# controller_board.net
KiCad netlist of a schematic drawn in EAGLE
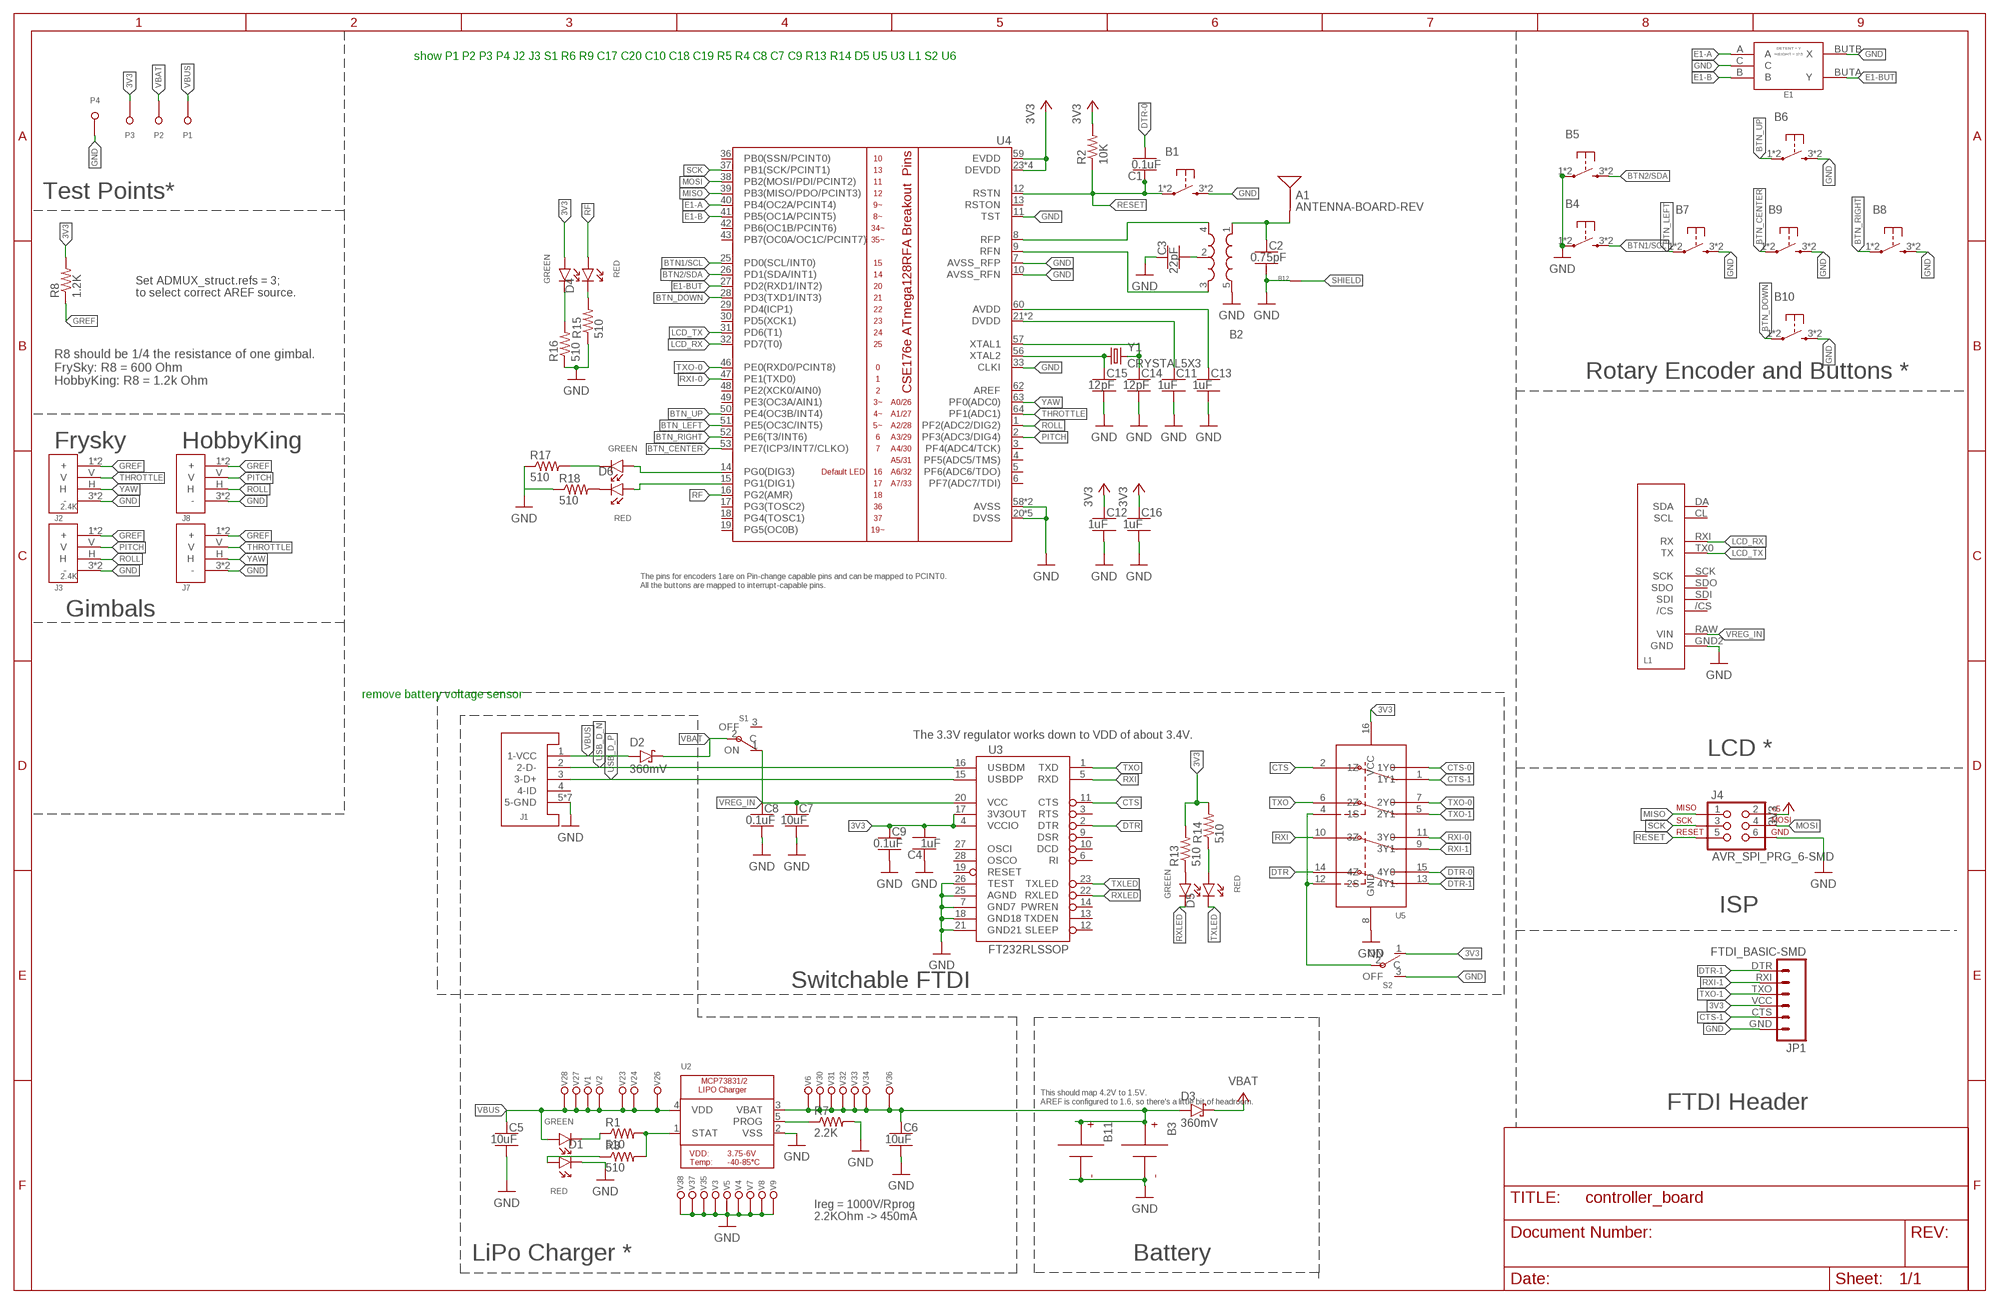
[diagram p0: schematic, sheet 1]

(export (version "E")
  (design (tool "Eeschema 10.0.6"))
  (components
    (comp (ref "A1")
      (value "ANTENNA-BOARD-REV")
      (footprint "eagle-import:ANT_PCB_2.4GHZ_NRF8001_1.6MM_1OZ_REV")
      (fields (field (name "CREATOR") "Swanson"))
      (libsource (lib "eagle-import") (part "ANTENNA-BOARD-REV"))
    )
    (comp (ref "B1")
      (value "PUSHBUTTON_-4.5X4.5")
      (footprint "eagle-import:4.5MM_TACTILE_SWITCH_TL3305AF160QG")
      (fields (field (name "CREATOR") "Swanson"))
      (libsource (lib "eagle-import") (part "PUSHBUTTON_-4.5X4.5"))
    )
    (comp (ref "B2")
      (value "BALUN0805")
      (footprint "eagle-import:BALUN")
      (fields
        (field (name "MFR") "Wurth Electronics Inc")
        (field (name "MPN") "748421245")
        (field (name "CREATOR") "Swanson")
        (field (name "REVIEWER") "Swanson")
      )
      (libsource (lib "eagle-import") (part "BALUN0805"))
    )
    (comp (ref "B3")
      (value "BATTERY-SPRING-SMD")
      (footprint "eagle-import:WIRE-TERMINAL-1X2-2.5MM-SMD-AVX-009276002021106")
      (libsource (lib "eagle-import") (part "BATTERY-SPRING-SMD"))
    )
    (comp (ref "B4")
      (value "PUSHBUTTON_-4.5X4.5")
      (footprint "eagle-import:4.5MM_TACTILE_SWITCH_TL3305AF160QG")
      (fields (field (name "CREATOR") "Swanson"))
      (libsource (lib "eagle-import") (part "PUSHBUTTON_-4.5X4.5"))
    )
    (comp (ref "B5")
      (value "PUSHBUTTON_-4.5X4.5")
      (footprint "eagle-import:4.5MM_TACTILE_SWITCH_TL3305AF160QG")
      (fields (field (name "CREATOR") "Swanson"))
      (libsource (lib "eagle-import") (part "PUSHBUTTON_-4.5X4.5"))
    )
    (comp (ref "B6")
      (value "PUSHBUTTON_-4.5X4.5")
      (footprint "eagle-import:4.5MM_TACTILE_SWITCH_TL3305AF160QG")
      (fields (field (name "CREATOR") "Swanson"))
      (libsource (lib "eagle-import") (part "PUSHBUTTON_-4.5X4.5"))
    )
    (comp (ref "B7")
      (value "PUSHBUTTON_-4.5X4.5")
      (footprint "eagle-import:4.5MM_TACTILE_SWITCH_TL3305AF160QG")
      (fields (field (name "CREATOR") "Swanson"))
      (libsource (lib "eagle-import") (part "PUSHBUTTON_-4.5X4.5"))
    )
    (comp (ref "B8")
      (value "PUSHBUTTON_-4.5X4.5")
      (footprint "eagle-import:4.5MM_TACTILE_SWITCH_TL3305AF160QG")
      (fields (field (name "CREATOR") "Swanson"))
      (libsource (lib "eagle-import") (part "PUSHBUTTON_-4.5X4.5"))
    )
    (comp (ref "B9")
      (value "PUSHBUTTON_-4.5X4.5")
      (footprint "eagle-import:4.5MM_TACTILE_SWITCH_TL3305AF160QG")
      (fields (field (name "CREATOR") "Swanson"))
      (libsource (lib "eagle-import") (part "PUSHBUTTON_-4.5X4.5"))
    )
    (comp (ref "B10")
      (value "PUSHBUTTON_-4.5X4.5")
      (footprint "eagle-import:4.5MM_TACTILE_SWITCH_TL3305AF160QG")
      (fields (field (name "CREATOR") "Swanson"))
      (libsource (lib "eagle-import") (part "PUSHBUTTON_-4.5X4.5"))
    )
    (comp (ref "B11")
      (value "BATTERY-SCREW-TERMINAL")
      (footprint "eagle-import:SCREW-TERMINAL-1X2-2.54MM")
      (fields (field (name "CREATOR") "Swanson"))
      (libsource (lib "eagle-import") (part "BATTERY-SCREW-TERMINAL"))
    )
    (comp (ref "B12")
      (value "NET_BRIDGE")
      (footprint "eagle-import:NET_BRIDGE")
      (fields (field (name "CREATOR") "Michael Gonzalez"))
      (libsource (lib "eagle-import") (part "NET_BRIDGE"))
    )
    (comp (ref "C1")
      (value "0.1uF")
      (footprint "eagle-import:CAPC2012X140_HS")
      (fields
        (field (name "MFR") "TDK")
        (field (name "MPN") "C2012X7R2A104K125AA")
        (field (name "CREATOR") "Swanson")
        (field (name "REVIEWER") "Swanson")
      )
      (libsource (lib "eagle-import") (part "CAPACITOR-NP_SMD-2012-0805_CERAMIC-0.1UF"))
    )
    (comp (ref "C2")
      (value "0.75pF")
      (footprint "eagle-import:CAPC2012X140_HS")
      (fields
        (field (name "MFR") "Murata Electronics North America")
        (field (name "MPN") "GQM2195C2AR75CB01D")
        (field (name "CREATOR") "Swanson")
        (field (name "REVIEWER") "Swanson")
      )
      (libsource (lib "eagle-import") (part "CAPACITOR-NP_SMD-2012-0805_CERAMIC-0.75PF"))
    )
    (comp (ref "C3")
      (value "22pF")
      (footprint "eagle-import:CAPC2012X140_HS")
      (fields
        (field (name "MFR") "Murata Electronics North America")
        (field (name "MPN") "GRM21A5C2E220JW01D")
        (field (name "CREATOR") "Swanson")
        (field (name "REVIEWER") "Swanson")
      )
      (libsource (lib "eagle-import") (part "CAPACITOR-NP_SMD-2012-0805_CERAMIC-22PF"))
    )
    (comp (ref "C4")
      (value "1uF")
      (footprint "eagle-import:CAPC2012X140_HS")
      (fields
        (field (name "MFR") "Taiyo Yuden")
        (field (name "MPN") "TMK212B7105KG-T")
        (field (name "CREATOR") "Swanson")
        (field (name "REVIEWER") "Swanson")
      )
      (libsource (lib "eagle-import") (part "CAPACITOR-NP_SMD-2012-0805_CERAMIC-1UF"))
    )
    (comp (ref "C5")
      (value "10uF")
      (footprint "eagle-import:CAPC2012X140_HS")
      (fields (field (name "CREATOR") "Swanson") (field (name "REVIEWER") "Swanson"))
      (libsource (lib "eagle-import") (part "CAPACITOR-NP_SMD-2012-0805_CERAMIC-10UF"))
    )
    (comp (ref "C6")
      (value "10uF")
      (footprint "eagle-import:CAPC2012X140_HS")
      (fields (field (name "CREATOR") "Swanson") (field (name "REVIEWER") "Swanson"))
      (libsource (lib "eagle-import") (part "CAPACITOR-NP_SMD-2012-0805_CERAMIC-10UF"))
    )
    (comp (ref "C7")
      (value "10uF")
      (footprint "eagle-import:CAPC2012X140_HS")
      (fields (field (name "CREATOR") "Swanson") (field (name "REVIEWER") "Swanson"))
      (libsource (lib "eagle-import") (part "CAPACITOR-NP_SMD-2012-0805_CERAMIC-10UF"))
    )
    (comp (ref "C8")
      (value "0.1uF")
      (footprint "eagle-import:CAPC2012X140_HS")
      (fields
        (field (name "MFR") "TDK")
        (field (name "MPN") "C2012X7R2A104K125AA")
        (field (name "CREATOR") "Swanson")
        (field (name "REVIEWER") "Swanson")
      )
      (libsource (lib "eagle-import") (part "CAPACITOR-NP_SMD-2012-0805_CERAMIC-0.1UF"))
    )
    (comp (ref "C9")
      (value "0.1uF")
      (footprint "eagle-import:CAPC2012X140_HS")
      (fields
        (field (name "MFR") "TDK")
        (field (name "MPN") "C2012X7R2A104K125AA")
        (field (name "CREATOR") "Swanson")
        (field (name "REVIEWER") "Swanson")
      )
      (libsource (lib "eagle-import") (part "CAPACITOR-NP_SMD-2012-0805_CERAMIC-0.1UF"))
    )
    (comp (ref "C11")
      (value "1uF")
      (footprint "eagle-import:CAPC2012X140_HS")
      (fields
        (field (name "MFR") "Taiyo Yuden")
        (field (name "MPN") "TMK212B7105KG-T")
        (field (name "CREATOR") "Swanson")
        (field (name "REVIEWER") "Swanson")
      )
      (libsource (lib "eagle-import") (part "CAPACITOR-NP_SMD-2012-0805_CERAMIC-1UF"))
    )
    (comp (ref "C12")
      (value "1uF")
      (footprint "eagle-import:CAPC2012X140_HS")
      (fields
        (field (name "MFR") "Taiyo Yuden")
        (field (name "MPN") "TMK212B7105KG-T")
        (field (name "CREATOR") "Swanson")
        (field (name "REVIEWER") "Swanson")
      )
      (libsource (lib "eagle-import") (part "CAPACITOR-NP_SMD-2012-0805_CERAMIC-1UF"))
    )
    (comp (ref "C13")
      (value "1uF")
      (footprint "eagle-import:CAPC2012X140_HS")
      (fields
        (field (name "MFR") "Taiyo Yuden")
        (field (name "MPN") "TMK212B7105KG-T")
        (field (name "CREATOR") "Swanson")
        (field (name "REVIEWER") "Swanson")
      )
      (libsource (lib "eagle-import") (part "CAPACITOR-NP_SMD-2012-0805_CERAMIC-1UF"))
    )
    (comp (ref "C14")
      (value "12pF")
      (footprint "eagle-import:CAPC2012X140_HS")
      (fields
        (field (name "MFR") "Murata Electronics North America")
        (field (name "MPN") "GRM21A5C2E120JW01D")
        (field (name "CREATOR") "Swanson")
        (field (name "REVIEWER") "Swanson")
      )
      (libsource (lib "eagle-import") (part "CAPACITOR-NP_SMD-2012-0805_CERAMIC-12PF"))
    )
    (comp (ref "C15")
      (value "12pF")
      (footprint "eagle-import:CAPC2012X140_HS")
      (fields
        (field (name "MFR") "Murata Electronics North America")
        (field (name "MPN") "GRM21A5C2E120JW01D")
        (field (name "CREATOR") "Swanson")
        (field (name "REVIEWER") "Swanson")
      )
      (libsource (lib "eagle-import") (part "CAPACITOR-NP_SMD-2012-0805_CERAMIC-12PF"))
    )
    (comp (ref "C16")
      (value "1uF")
      (footprint "eagle-import:CAPC2012X140_HS")
      (fields
        (field (name "MFR") "Taiyo Yuden")
        (field (name "MPN") "TMK212B7105KG-T")
        (field (name "CREATOR") "Swanson")
        (field (name "REVIEWER") "Swanson")
      )
      (libsource (lib "eagle-import") (part "CAPACITOR-NP_SMD-2012-0805_CERAMIC-1UF"))
    )
    (comp (ref "D1")
      (value "LED-2X-GREEN/RED")
      (footprint "eagle-import:LED-2X-LTST-C155")
      (fields
        (field (name "COLOR2") "RED")
        (field (name "COLOR1") "GREEN")
        (field (name "CREATOR") "Swanson")
      )
      (libsource (lib "eagle-import") (part "LED-2X-GREEN/RED"))
    )
    (comp (ref "D2")
      (value "360mV")
      (footprint "eagle-import:SOD3716X135_HS")
      (fields
        (field (name "MFR") "Toshiba Semiconductor and Storage")
        (field (name "MPN") "CRS08(TE85L,Q,M)")
        (field (name "CREATOR") "Swanson")
        (field (name "REVIEWER") "Swanson")
      )
      (libsource (lib "eagle-import") (part "DIODE-SCHOTTKY_SMD-SOD123-360MV"))
    )
    (comp (ref "D3")
      (value "360mV")
      (footprint "eagle-import:SOD3716X135_HS")
      (fields
        (field (name "MFR") "Toshiba Semiconductor and Storage")
        (field (name "MPN") "CRS08(TE85L,Q,M)")
        (field (name "CREATOR") "Swanson")
        (field (name "REVIEWER") "Swanson")
      )
      (libsource (lib "eagle-import") (part "DIODE-SCHOTTKY_SMD-SOD123-360MV"))
    )
    (comp (ref "D4")
      (value "LED-2X-GREEN/RED")
      (footprint "eagle-import:LED-2X-LTST-C155")
      (fields
        (field (name "COLOR2") "RED")
        (field (name "COLOR1") "GREEN")
        (field (name "CREATOR") "Swanson")
      )
      (libsource (lib "eagle-import") (part "LED-2X-GREEN/RED"))
    )
    (comp (ref "D5")
      (value "LED-2X-GREEN/RED")
      (footprint "eagle-import:LED-2X-LTST-C155")
      (fields
        (field (name "COLOR2") "RED")
        (field (name "COLOR1") "GREEN")
        (field (name "CREATOR") "Swanson")
      )
      (libsource (lib "eagle-import") (part "LED-2X-GREEN/RED"))
    )
    (comp (ref "D6")
      (value "LED-2X-GREEN/RED")
      (footprint "eagle-import:LED-2X-LTST-C155")
      (fields
        (field (name "COLOR2") "RED")
        (field (name "COLOR1") "GREEN")
        (field (name "CREATOR") "Swanson")
      )
      (libsource (lib "eagle-import") (part "LED-2X-GREEN/RED"))
    )
    (comp (ref "E1")
      (value "ROTARY-ENCODER-W/BUTTON-BOURNS-PEC12R-4217F")
      (footprint "eagle-import:BOURNS-PEC12R")
      (fields (field (name "DETENT") "Y") (field (name "HEIGHT") "17.5") (field (name "CREATOR") "Swanson"))
      (libsource (lib "eagle-import") (part "ROTARY-ENCODER-W/BUTTON-BOURNS-PEC12R-4217F"))
    )
    (comp (ref "J1")
      (value "USB-MICROA-AMPHENOL-10118192-0001LF")
      (footprint "eagle-import:USB-MICROA-10118192-0001LF")
      (fields (field (name "CREATOR") "Swanson"))
      (libsource (lib "eagle-import") (part "USB-MICROA-AMPHENOL-10118192-0001LF"))
    )
    (comp (ref "J2")
      (value "2.4K")
      (footprint "eagle-import:JST-13-PTH")
      (fields (field (name "CREATOR") "Swanson"))
      (libsource (lib "eagle-import") (part "FRSKY-GIMBAL-FRYSKY"))
    )
    (comp (ref "J3")
      (value "2.4K")
      (footprint "eagle-import:JST-13-PTH")
      (fields (field (name "SPICEPREFIX") "E") (field (name "CREATOR") "Swanson"))
      (libsource (lib "eagle-import") (part "FRSKY-GIMBAL-FRYSKY"))
    )
    (comp (ref "J4")
      (value "AVR_SPI_PRG_6-SMD")
      (footprint "eagle-import:2X3-SMD")
      (fields (field (name "CREATOR") "Swanson"))
      (libsource (lib "eagle-import") (part "AVR_SPI_PRG_6-SMD"))
    )
    (comp (ref "J7")
      (value "FRSKY-GIMBAL-2X-SERVO-SMD")
      (footprint "eagle-import:2X-SERVO-SMD")
      (libsource (lib "eagle-import") (part "FRSKY-GIMBAL-2X-SERVO-SMD"))
    )
    (comp (ref "J8")
      (value "FRSKY-GIMBAL-2X-SERVO-SMD")
      (footprint "eagle-import:2X-SERVO-SMD")
      (libsource (lib "eagle-import") (part "FRSKY-GIMBAL-2X-SERVO-SMD"))
    )
    (comp (ref "JP1")
      (value "FTDI_BASIC-SMD")
      (footprint "eagle-import:FTDI-BASIC-SMD")
      (libsource (lib "eagle-import") (part "FTDI_BASIC-SMD"))
    )
    (comp (ref "L1")
      (value "SPARKFUN_SERLCD_SERIAL_REDUCED-SMD")
      (footprint "eagle-import:SPARKFUN_SERLCD_16X2_REDUCED_SMD")
      (fields (field (name "CREATOR") "Swanson"))
      (libsource (lib "eagle-import") (part "SPARKFUN_SERLCD_SERIAL_REDUCED-SMD"))
    )
    (comp (ref "P1")
      (value "TEST-POINT")
      (footprint "eagle-import:TEST-POINT-KEYSTONE-5000")
      (fields (field (name "CREATOR") "Swanson"))
      (libsource (lib "eagle-import") (part "TEST-POINT"))
    )
    (comp (ref "P2")
      (value "TEST-POINT")
      (footprint "eagle-import:TEST-POINT-KEYSTONE-5000")
      (fields (field (name "CREATOR") "Swanson"))
      (libsource (lib "eagle-import") (part "TEST-POINT"))
    )
    (comp (ref "P3")
      (value "TEST-POINT")
      (footprint "eagle-import:TEST-POINT-KEYSTONE-5000")
      (fields (field (name "CREATOR") "Swanson"))
      (libsource (lib "eagle-import") (part "TEST-POINT"))
    )
    (comp (ref "P4")
      (value "TEST-POINT")
      (footprint "eagle-import:TEST-POINT-KEYSTONE-5000")
      (fields (field (name "CREATOR") "Swanson"))
      (libsource (lib "eagle-import") (part "TEST-POINT"))
    )
    (comp (ref "R1")
      (value "510")
      (footprint "eagle-import:RESC2012X60_HS")
      (fields (field (name "CREATOR") "SWANSON"))
      (libsource (lib "eagle-import") (part "RESISTOR_SMD-2012-0805-510"))
    )
    (comp (ref "R2")
      (value "10K")
      (footprint "eagle-import:RESC2012X60_HS")
      (fields
        (field (name "MFR") "Yageo")
        (field (name "MPN") "RC0805JR-0710KL")
        (field (name "CREATOR") "Swanson")
        (field (name "REVIEWER") "Swanson")
      )
      (libsource (lib "eagle-import") (part "RESISTOR_SMD-2012-0805-10K"))
    )
    (comp (ref "R3")
      (value "510")
      (footprint "eagle-import:RESC2012X60_HS")
      (fields (field (name "CREATOR") "SWANSON"))
      (libsource (lib "eagle-import") (part "RESISTOR_SMD-2012-0805-510"))
    )
    (comp (ref "R7")
      (value "2.2K")
      (footprint "eagle-import:RESC2012X60_HS")
      (fields (field (name "CREATOR") "SWANSON"))
      (libsource (lib "eagle-import") (part "RESISTOR_SMD-2012-0805-2.2K"))
    )
    (comp (ref "R8")
      (value "1.2K")
      (footprint "eagle-import:RESC2012X60_HS")
      (fields (field (name "CREATOR") "Swanson"))
      (libsource (lib "eagle-import") (part "RESISTOR_SMD-2012-0805-1.2K"))
    )
    (comp (ref "R13")
      (value "510")
      (footprint "eagle-import:RESC2012X60_HS")
      (fields (field (name "CREATOR") "SWANSON"))
      (libsource (lib "eagle-import") (part "RESISTOR_SMD-2012-0805-510"))
    )
    (comp (ref "R14")
      (value "510")
      (footprint "eagle-import:RESC2012X60_HS")
      (fields (field (name "CREATOR") "SWANSON"))
      (libsource (lib "eagle-import") (part "RESISTOR_SMD-2012-0805-510"))
    )
    (comp (ref "R15")
      (value "510")
      (footprint "eagle-import:RESC2012X60_HS")
      (fields (field (name "CREATOR") "SWANSON"))
      (libsource (lib "eagle-import") (part "RESISTOR_SMD-2012-0805-510"))
    )
    (comp (ref "R16")
      (value "510")
      (footprint "eagle-import:RESC2012X60_HS")
      (fields (field (name "CREATOR") "SWANSON"))
      (libsource (lib "eagle-import") (part "RESISTOR_SMD-2012-0805-510"))
    )
    (comp (ref "R17")
      (value "510")
      (footprint "eagle-import:RESC2012X60_HS")
      (fields (field (name "CREATOR") "SWANSON"))
      (libsource (lib "eagle-import") (part "RESISTOR_SMD-2012-0805-510"))
    )
    (comp (ref "R18")
      (value "510")
      (footprint "eagle-import:RESC2012X60_HS")
      (fields (field (name "CREATOR") "SWANSON"))
      (libsource (lib "eagle-import") (part "RESISTOR_SMD-2012-0805-510"))
    )
    (comp (ref "S1")
      (value "POWER-SWITCH-MFS201N-9-Z-SMD-VERTICAL")
      (footprint "eagle-import:JS102011JCQN")
      (fields (field (name "CREATOR") "Swanson"))
      (libsource (lib "eagle-import") (part "POWER-SWITCH-MFS201N-9-Z-SMD-VERTICAL"))
    )
    (comp (ref "S2")
      (value "POWER-SWITCH-MFS201N-9-Z-SMD-VERTICAL")
      (footprint "eagle-import:JS102011JCQN")
      (fields (field (name "CREATOR") "Swanson"))
      (libsource (lib "eagle-import") (part "POWER-SWITCH-MFS201N-9-Z-SMD-VERTICAL"))
    )
    (comp (ref "U2")
      (value "MCP73831T-2ACI/OT")
      (footprint "eagle-import:SOT23-5")
      (fields (field (name "CREATOR") "Adafruit"))
      (libsource (lib "eagle-import") (part "MCP73831/2"))
    )
    (comp (ref "U3")
      (value "FT232RLSSOP")
      (footprint "eagle-import:SSOP28DB")
      (fields (field (name "CREATOR") "Swanson"))
      (libsource (lib "eagle-import") (part "FT232RLSSOP"))
    )
    (comp (ref "U4")
      (value "ATMEGA128RFA1")
      (footprint "eagle-import:QFN-64")
      (fields
        (field (name "MFR") "Atmel")
        (field (name "MPN") "ATMEGA128RFA1-ZUR00")
        (field (name "CREATOR") "Swanson")
        (field (name "REVIEWER") "Swanson")
      )
      (libsource (lib "eagle-import") (part "ATMEGA128RFA1"))
    )
    (comp (ref "U5")
      (value "DPDT-X2")
      (footprint "eagle-import:SOP65P640X110-16")
      (fields (field (name "CREATOR") "Swanson"))
      (libsource (lib "eagle-import") (part "DPDT-X2"))
    )
    (comp (ref "V1")
      (value "LOCKED-VIA-0.2")
      (footprint "eagle-import:VIA-0.2MM")
      (fields (field (name "CREATOR") "Swanson"))
      (libsource (lib "eagle-import") (part "LOCKED-VIA-0.2"))
    )
    (comp (ref "V2")
      (value "LOCKED-VIA-0.2")
      (footprint "eagle-import:VIA-0.2MM")
      (fields (field (name "CREATOR") "Swanson"))
      (libsource (lib "eagle-import") (part "LOCKED-VIA-0.2"))
    )
    (comp (ref "V3")
      (value "LOCKED-VIA-0.2")
      (footprint "eagle-import:VIA-0.2MM")
      (fields (field (name "CREATOR") "Swanson"))
      (libsource (lib "eagle-import") (part "LOCKED-VIA-0.2"))
    )
    (comp (ref "V4")
      (value "LOCKED-VIA-0.2")
      (footprint "eagle-import:VIA-0.2MM")
      (fields (field (name "CREATOR") "Swanson"))
      (libsource (lib "eagle-import") (part "LOCKED-VIA-0.2"))
    )
    (comp (ref "V5")
      (value "LOCKED-VIA-0.2")
      (footprint "eagle-import:VIA-0.2MM")
      (fields (field (name "CREATOR") "Swanson"))
      (libsource (lib "eagle-import") (part "LOCKED-VIA-0.2"))
    )
    (comp (ref "V6")
      (value "LOCKED-VIA-0.2")
      (footprint "eagle-import:VIA-0.2MM")
      (fields (field (name "CREATOR") "Swanson"))
      (libsource (lib "eagle-import") (part "LOCKED-VIA-0.2"))
    )
    (comp (ref "V7")
      (value "LOCKED-VIA-0.2")
      (footprint "eagle-import:VIA-0.2MM")
      (fields (field (name "CREATOR") "Swanson"))
      (libsource (lib "eagle-import") (part "LOCKED-VIA-0.2"))
    )
    (comp (ref "V8")
      (value "LOCKED-VIA-0.2")
      (footprint "eagle-import:VIA-0.2MM")
      (fields (field (name "CREATOR") "Swanson"))
      (libsource (lib "eagle-import") (part "LOCKED-VIA-0.2"))
    )
    (comp (ref "V9")
      (value "LOCKED-VIA-0.2")
      (footprint "eagle-import:VIA-0.2MM")
      (fields (field (name "CREATOR") "Swanson"))
      (libsource (lib "eagle-import") (part "LOCKED-VIA-0.2"))
    )
    (comp (ref "V23")
      (value "LOCKED-VIA-0.2")
      (footprint "eagle-import:VIA-0.2MM")
      (fields (field (name "CREATOR") "Swanson"))
      (libsource (lib "eagle-import") (part "LOCKED-VIA-0.2"))
    )
    (comp (ref "V24")
      (value "LOCKED-VIA-0.2")
      (footprint "eagle-import:VIA-0.2MM")
      (fields (field (name "CREATOR") "Swanson"))
      (libsource (lib "eagle-import") (part "LOCKED-VIA-0.2"))
    )
    (comp (ref "V26")
      (value "LOCKED-VIA-0.2")
      (footprint "eagle-import:VIA-0.2MM")
      (fields (field (name "CREATOR") "Swanson"))
      (libsource (lib "eagle-import") (part "LOCKED-VIA-0.2"))
    )
    (comp (ref "V27")
      (value "LOCKED-VIA-0.2")
      (footprint "eagle-import:VIA-0.2MM")
      (fields (field (name "CREATOR") "Swanson"))
      (libsource (lib "eagle-import") (part "LOCKED-VIA-0.2"))
    )
    (comp (ref "V28")
      (value "LOCKED-VIA-0.2")
      (footprint "eagle-import:VIA-0.2MM")
      (fields (field (name "CREATOR") "Swanson"))
      (libsource (lib "eagle-import") (part "LOCKED-VIA-0.2"))
    )
    (comp (ref "V30")
      (value "LOCKED-VIA-0.2")
      (footprint "eagle-import:VIA-0.2MM")
      (fields (field (name "CREATOR") "Swanson"))
      (libsource (lib "eagle-import") (part "LOCKED-VIA-0.2"))
    )
    (comp (ref "V31")
      (value "LOCKED-VIA-0.2")
      (footprint "eagle-import:VIA-0.2MM")
      (fields (field (name "CREATOR") "Swanson"))
      (libsource (lib "eagle-import") (part "LOCKED-VIA-0.2"))
    )
    (comp (ref "V32")
      (value "LOCKED-VIA-0.2")
      (footprint "eagle-import:VIA-0.2MM")
      (fields (field (name "CREATOR") "Swanson"))
      (libsource (lib "eagle-import") (part "LOCKED-VIA-0.2"))
    )
    (comp (ref "V33")
      (value "LOCKED-VIA-0.2")
      (footprint "eagle-import:VIA-0.2MM")
      (fields (field (name "CREATOR") "Swanson"))
      (libsource (lib "eagle-import") (part "LOCKED-VIA-0.2"))
    )
    (comp (ref "V34")
      (value "LOCKED-VIA-0.2")
      (footprint "eagle-import:VIA-0.2MM")
      (fields (field (name "CREATOR") "Swanson"))
      (libsource (lib "eagle-import") (part "LOCKED-VIA-0.2"))
    )
    (comp (ref "V35")
      (value "LOCKED-VIA-0.2")
      (footprint "eagle-import:VIA-0.2MM")
      (fields (field (name "CREATOR") "Swanson"))
      (libsource (lib "eagle-import") (part "LOCKED-VIA-0.2"))
    )
    (comp (ref "V36")
      (value "LOCKED-VIA-0.2")
      (footprint "eagle-import:VIA-0.2MM")
      (fields (field (name "CREATOR") "Swanson"))
      (libsource (lib "eagle-import") (part "LOCKED-VIA-0.2"))
    )
    (comp (ref "V37")
      (value "LOCKED-VIA-0.2")
      (footprint "eagle-import:VIA-0.2MM")
      (fields (field (name "CREATOR") "Swanson"))
      (libsource (lib "eagle-import") (part "LOCKED-VIA-0.2"))
    )
    (comp (ref "V38")
      (value "LOCKED-VIA-0.2")
      (footprint "eagle-import:VIA-0.2MM")
      (fields (field (name "CREATOR") "Swanson"))
      (libsource (lib "eagle-import") (part "LOCKED-VIA-0.2"))
    )
    (comp (ref "Y1")
      (value "CRYSTAL5X3")
      (footprint "eagle-import:CRYSTAL-SMD-5X3")
      (fields
        (field (name "MFR") "Abracon LLC")
        (field (name "MPN") "ABM3B-16.000MHZ-B2-T")
        (field (name "CREATOR") "Swanson")
        (field (name "REVIEWER") "Swanson")
      )
      (libsource (lib "eagle-import") (part "CRYSTAL5X3"))
    )
  )
  (nets
    (net (code "1") (name "3V3") (class "Default")
      (node (ref "C12") (pin "1") (pinfunction "1_1") (pintype "passive"))
      (node (ref "C16") (pin "1") (pinfunction "1_1") (pintype "passive"))
      (node (ref "C4") (pin "2") (pinfunction "2_2") (pintype "passive"))
      (node (ref "C9") (pin "1") (pinfunction "1_1") (pintype "passive"))
      (node (ref "D4") (pin "A2") (pinfunction "A2_A2") (pintype "passive"))
      (node (ref "J4") (pin "2") (pinfunction "2_2") (pintype "passive"))
      (node (ref "JP1") (pin "VCC") (pinfunction "4_VCC") (pintype "passive"))
      (node (ref "P3") (pin "T") (pinfunction "T_T") (pintype "bidirectional"))
      (node (ref "R13") (pin "2") (pinfunction "2_2") (pintype "passive"))
      (node (ref "R14") (pin "2") (pinfunction "2_2") (pintype "passive"))
      (node (ref "R2") (pin "2") (pinfunction "2_2") (pintype "passive"))
      (node (ref "R8") (pin "2") (pinfunction "2_2") (pintype "passive"))
      (node (ref "S2") (pin "1") (pinfunction "ON_1") (pintype "bidirectional"))
      (node (ref "U3") (pin "17") (pinfunction "3V3OUT_17") (pintype "output"))
      (node (ref "U3") (pin "4") (pinfunction "VCCIO_4") (pintype "power_in"))
      (node (ref "U4") (pin "23") (pinfunction "DEVDD_23") (pintype "bidirectional"))
      (node (ref "U4") (pin "34") (pinfunction "DEVDD_34") (pintype "bidirectional"))
      (node (ref "U4") (pin "44") (pinfunction "DEVDD_44") (pintype "bidirectional"))
      (node (ref "U4") (pin "54") (pinfunction "DEVDD_54") (pintype "bidirectional"))
      (node (ref "U4") (pin "59") (pinfunction "EVDD_59") (pintype "bidirectional"))
      (node (ref "U5") (pin "16") (pinfunction "VCC_16") (pintype "bidirectional"))
    )
    (net (code "2") (name "BTN1{slash}SCL") (class "Default")
      (node (ref "B4") (pin "3") (pinfunction "2_3") (pintype "passive"))
      (node (ref "B4") (pin "4") (pinfunction "2_4") (pintype "passive"))
      (node (ref "U4") (pin "25") (pinfunction "PD0(SCL/INT0)_25") (pintype "bidirectional"))
    )
    (net (code "3") (name "BTN2{slash}SDA") (class "Default")
      (node (ref "B5") (pin "3") (pinfunction "2_3") (pintype "passive"))
      (node (ref "B5") (pin "4") (pinfunction "2_4") (pintype "passive"))
      (node (ref "U4") (pin "26") (pinfunction "PD1(SDA/INT1)_26") (pintype "bidirectional"))
    )
    (net (code "4") (name "BTN_CENTER") (class "Default")
      (node (ref "B9") (pin "1") (pinfunction "1_1") (pintype "passive"))
      (node (ref "B9") (pin "2") (pinfunction "1_2") (pintype "passive"))
      (node (ref "U4") (pin "53") (pinfunction "PE7(ICP3/INT7/CLKO)_53") (pintype "bidirectional"))
    )
    (net (code "5") (name "BTN_DOWN") (class "Default")
      (node (ref "B10") (pin "1") (pinfunction "1_1") (pintype "passive"))
      (node (ref "B10") (pin "2") (pinfunction "1_2") (pintype "passive"))
      (node (ref "U4") (pin "28") (pinfunction "PD3(TXD1/INT3)_28") (pintype "bidirectional"))
    )
    (net (code "6") (name "BTN_LEFT") (class "Default")
      (node (ref "B7") (pin "1") (pinfunction "1_1") (pintype "passive"))
      (node (ref "B7") (pin "2") (pinfunction "1_2") (pintype "passive"))
      (node (ref "U4") (pin "51") (pinfunction "PE5(OC3C/INT5)_51") (pintype "bidirectional"))
    )
    (net (code "7") (name "BTN_RIGHT") (class "Default")
      (node (ref "B8") (pin "1") (pinfunction "1_1") (pintype "passive"))
      (node (ref "B8") (pin "2") (pinfunction "1_2") (pintype "passive"))
      (node (ref "U4") (pin "52") (pinfunction "PE6(T3/INT6)_52") (pintype "bidirectional"))
    )
    (net (code "8") (name "BTN_UP") (class "Default")
      (node (ref "B6") (pin "1") (pinfunction "1_1") (pintype "passive"))
      (node (ref "B6") (pin "2") (pinfunction "1_2") (pintype "passive"))
      (node (ref "U4") (pin "50") (pinfunction "PE4(OC3B/INT4)_50") (pintype "bidirectional"))
    )
    (net (code "9") (name "CTS") (class "Default")
      (node (ref "U3") (pin "11") (pinfunction "CTS_11") (pintype "input"))
      (node (ref "U5") (pin "2") (pinfunction "1Z_2") (pintype "bidirectional"))
    )
    (net (code "10") (name "CTS-0") (class "Default")
      (node (ref "U5") (pin "3") (pinfunction "1Y0_3") (pintype "bidirectional"))
    )
    (net (code "11") (name "CTS-1") (class "Default")
      (node (ref "JP1") (pin "CTS") (pinfunction "5_CTS") (pintype "passive"))
      (node (ref "U5") (pin "1") (pinfunction "1Y1_1") (pintype "bidirectional"))
    )
    (net (code "12") (name "DTR") (class "Default")
      (node (ref "U3") (pin "2") (pinfunction "DTR_2") (pintype "output"))
      (node (ref "U5") (pin "14") (pinfunction "4Z_14") (pintype "bidirectional"))
    )
    (net (code "13") (name "DTR-0") (class "Default")
      (node (ref "C1") (pin "2") (pinfunction "2_2") (pintype "passive"))
      (node (ref "U5") (pin "15") (pinfunction "4Y0_15") (pintype "bidirectional"))
    )
    (net (code "14") (name "DTR-1") (class "Default")
      (node (ref "JP1") (pin "DTR") (pinfunction "1_DTR") (pintype "passive"))
      (node (ref "U5") (pin "13") (pinfunction "4Y1_13") (pintype "bidirectional"))
    )
    (net (code "15") (name "E1-A") (class "Default")
      (node (ref "E1") (pin "A") (pinfunction "A_A") (pintype "bidirectional"))
      (node (ref "U4") (pin "40") (pinfunction "PB4(OC2A/PCINT4)_40") (pintype "bidirectional"))
    )
    (net (code "16") (name "E1-B") (class "Default")
      (node (ref "E1") (pin "B") (pinfunction "B_B") (pintype "bidirectional"))
      (node (ref "U4") (pin "41") (pinfunction "PB5(OC1A/PCINT5)_41") (pintype "bidirectional"))
    )
    (net (code "17") (name "E1-BUT") (class "Default")
      (node (ref "E1") (pin "BUTA") (pinfunction "Y_BUTA") (pintype "bidirectional"))
      (node (ref "U4") (pin "27") (pinfunction "PD2(RXD1/INT2)_27") (pintype "bidirectional"))
    )
    (net (code "18") (name "GND") (class "Default")
      (node (ref "B1") (pin "3") (pinfunction "2_3") (pintype "passive"))
      (node (ref "B1") (pin "4") (pinfunction "2_4") (pintype "passive"))
      (node (ref "B10") (pin "3") (pinfunction "2_3") (pintype "passive"))
      (node (ref "B10") (pin "4") (pinfunction "2_4") (pintype "passive"))
      (node (ref "B11") (pin "1") (pinfunction "N_1") (pintype "bidirectional"))
      (node (ref "B12") (pin "P1") (pinfunction "P1_P1") (pintype "bidirectional"))
      (node (ref "B2") (pin "5") (pinfunction "GND_5") (pintype "bidirectional"))
      (node (ref "B3") (pin "2A") (pinfunction "N_2A") (pintype "bidirectional"))
      (node (ref "B3") (pin "2B") (pinfunction "N_2B") (pintype "bidirectional"))
      (node (ref "B4") (pin "1") (pinfunction "1_1") (pintype "passive"))
      (node (ref "B4") (pin "2") (pinfunction "1_2") (pintype "passive"))
      (node (ref "B5") (pin "1") (pinfunction "1_1") (pintype "passive"))
      (node (ref "B5") (pin "2") (pinfunction "1_2") (pintype "passive"))
      (node (ref "B6") (pin "3") (pinfunction "2_3") (pintype "passive"))
      (node (ref "B6") (pin "4") (pinfunction "2_4") (pintype "passive"))
      (node (ref "B7") (pin "3") (pinfunction "2_3") (pintype "passive"))
      (node (ref "B7") (pin "4") (pinfunction "2_4") (pintype "passive"))
      (node (ref "B8") (pin "3") (pinfunction "2_3") (pintype "passive"))
      (node (ref "B8") (pin "4") (pinfunction "2_4") (pintype "passive"))
      (node (ref "B9") (pin "3") (pinfunction "2_3") (pintype "passive"))
      (node (ref "B9") (pin "4") (pinfunction "2_4") (pintype "passive"))
      (node (ref "C11") (pin "2") (pinfunction "2_2") (pintype "passive"))
      (node (ref "C12") (pin "2") (pinfunction "2_2") (pintype "passive"))
      (node (ref "C13") (pin "2") (pinfunction "2_2") (pintype "passive"))
      (node (ref "C14") (pin "2") (pinfunction "2_2") (pintype "passive"))
      (node (ref "C15") (pin "2") (pinfunction "2_2") (pintype "passive"))
      (node (ref "C16") (pin "2") (pinfunction "2_2") (pintype "passive"))
      (node (ref "C2") (pin "2") (pinfunction "2_2") (pintype "passive"))
      (node (ref "C3") (pin "1") (pinfunction "1_1") (pintype "passive"))
      (node (ref "C4") (pin "1") (pinfunction "1_1") (pintype "passive"))
      (node (ref "C5") (pin "2") (pinfunction "2_2") (pintype "passive"))
      (node (ref "C6") (pin "2") (pinfunction "2_2") (pintype "passive"))
      (node (ref "C7") (pin "2") (pinfunction "2_2") (pintype "passive"))
      (node (ref "C8") (pin "2") (pinfunction "2_2") (pintype "passive"))
      (node (ref "C9") (pin "2") (pinfunction "2_2") (pintype "passive"))
      (node (ref "D1") (pin "C1") (pinfunction "C1_C1") (pintype "passive"))
      (node (ref "E1") (pin "BUTB") (pinfunction "X_BUTB") (pintype "bidirectional"))
      (node (ref "E1") (pin "C") (pinfunction "C_C") (pintype "bidirectional"))
      (node (ref "J1") (pin "10") (pinfunction "5-GND_10") (pintype "bidirectional"))
      (node (ref "J1") (pin "11") (pinfunction "5-GND_11") (pintype "bidirectional"))
      (node (ref "J1") (pin "5") (pinfunction "5-GND_5") (pintype "bidirectional"))
      (node (ref "J1") (pin "6") (pinfunction "5-GND_6") (pintype "bidirectional"))
      (node (ref "J1") (pin "7") (pinfunction "5-GND_7") (pintype "bidirectional"))
      (node (ref "J1") (pin "8") (pinfunction "5-GND_8") (pintype "bidirectional"))
      (node (ref "J1") (pin "9") (pinfunction "5-GND_9") (pintype "bidirectional"))
      (node (ref "J2") (pin "3") (pinfunction "-_3") (pintype "bidirectional"))
      (node (ref "J2") (pin "6") (pinfunction "-_6") (pintype "bidirectional"))
      (node (ref "J3") (pin "3") (pinfunction "-_3") (pintype "bidirectional"))
      (node (ref "J3") (pin "6") (pinfunction "-_6") (pintype "bidirectional"))
      (node (ref "J4") (pin "6") (pinfunction "6_6") (pintype "passive"))
      (node (ref "J7") (pin "3") (pinfunction "-_3") (pintype "bidirectional"))
      (node (ref "J7") (pin "6") (pinfunction "-_6") (pintype "bidirectional"))
      (node (ref "J8") (pin "3") (pinfunction "-_3") (pintype "bidirectional"))
      (node (ref "J8") (pin "6") (pinfunction "-_6") (pintype "bidirectional"))
      (node (ref "JP1") (pin "GND") (pinfunction "6_GND") (pintype "passive"))
      (node (ref "L1") (pin "GND2") (pinfunction "GND_GND2") (pintype "bidirectional"))
      (node (ref "P4") (pin "T") (pinfunction "T_T") (pintype "bidirectional"))
      (node (ref "R15") (pin "1") (pinfunction "1_1") (pintype "passive"))
      (node (ref "R16") (pin "1") (pinfunction "1_1") (pintype "passive"))
      (node (ref "R17") (pin "1") (pinfunction "1_1") (pintype "passive"))
      (node (ref "R18") (pin "1") (pinfunction "1_1") (pintype "passive"))
      (node (ref "R7") (pin "2") (pinfunction "2_2") (pintype "passive"))
      (node (ref "S2") (pin "3") (pinfunction "OFF_3") (pintype "bidirectional"))
      (node (ref "U2") (pin "2") (pinfunction "VSS_2") (pintype "power_in"))
      (node (ref "U3") (pin "18") (pinfunction "GND18_18") (pintype "power_in"))
      (node (ref "U3") (pin "21") (pinfunction "GND21_21") (pintype "power_in"))
      (node (ref "U3") (pin "25") (pinfunction "AGND_25") (pintype "power_in"))
      (node (ref "U3") (pin "26") (pinfunction "TEST_26") (pintype "input"))
      (node (ref "U3") (pin "7") (pinfunction "GND7_7") (pintype "power_in"))
      (node (ref "U4") (pin "10") (pinfunction "AVSS_RFN_10") (pintype "bidirectional"))
      (node (ref "U4") (pin "11") (pinfunction "TST_11") (pintype "bidirectional"))
      (node (ref "U4") (pin "20") (pinfunction "DVSS_20") (pintype "bidirectional"))
      (node (ref "U4") (pin "24") (pinfunction "DVSS_24") (pintype "bidirectional"))
      (node (ref "U4") (pin "33") (pinfunction "CLKI_33") (pintype "bidirectional"))
      (node (ref "U4") (pin "35") (pinfunction "DVSS_35") (pintype "bidirectional"))
      (node (ref "U4") (pin "45") (pinfunction "DVSS_45") (pintype "bidirectional"))
      (node (ref "U4") (pin "55") (pinfunction "DVSS_55") (pintype "bidirectional"))
      (node (ref "U4") (pin "58") (pinfunction "AVSS_58") (pintype "bidirectional"))
      (node (ref "U4") (pin "61") (pinfunction "AVSS_61") (pintype "bidirectional"))
      (node (ref "U4") (pin "7") (pinfunction "AVSS_RFP_7") (pintype "bidirectional"))
      (node (ref "U5") (pin "8") (pinfunction "GND_8") (pintype "bidirectional"))
      (node (ref "V3") (pin "P1") (pinfunction "N_P1") (pintype "bidirectional"))
      (node (ref "V35") (pin "P1") (pinfunction "N_P1") (pintype "bidirectional"))
      (node (ref "V37") (pin "P1") (pinfunction "N_P1") (pintype "bidirectional"))
      (node (ref "V38") (pin "P1") (pinfunction "N_P1") (pintype "bidirectional"))
      (node (ref "V4") (pin "P1") (pinfunction "N_P1") (pintype "bidirectional"))
      (node (ref "V5") (pin "P1") (pinfunction "N_P1") (pintype "bidirectional"))
      (node (ref "V7") (pin "P1") (pinfunction "N_P1") (pintype "bidirectional"))
      (node (ref "V8") (pin "P1") (pinfunction "N_P1") (pintype "bidirectional"))
      (node (ref "V9") (pin "P1") (pinfunction "N_P1") (pintype "bidirectional"))
    )
    (net (code "19") (name "GREF") (class "Default")
      (node (ref "J2") (pin "1") (pinfunction "+_1") (pintype "bidirectional"))
      (node (ref "J2") (pin "4") (pinfunction "+_4") (pintype "bidirectional"))
      (node (ref "J3") (pin "1") (pinfunction "+_1") (pintype "bidirectional"))
      (node (ref "J3") (pin "4") (pinfunction "+_4") (pintype "bidirectional"))
      (node (ref "J7") (pin "1") (pinfunction "+_1") (pintype "bidirectional"))
      (node (ref "J7") (pin "4") (pinfunction "+_4") (pintype "bidirectional"))
      (node (ref "J8") (pin "1") (pinfunction "+_1") (pintype "bidirectional"))
      (node (ref "J8") (pin "4") (pinfunction "+_4") (pintype "bidirectional"))
      (node (ref "R8") (pin "1") (pinfunction "1_1") (pintype "passive"))
    )
    (net (code "20") (name "LCD_RX") (class "Default")
      (node (ref "L1") (pin "RXI") (pinfunction "RX_RXI") (pintype "bidirectional"))
      (node (ref "U4") (pin "32") (pinfunction "PD7(T0)_32") (pintype "bidirectional"))
    )
    (net (code "21") (name "LCD_TX") (class "Default")
      (node (ref "L1") (pin "TX0") (pinfunction "TX_TX0") (pintype "bidirectional"))
      (node (ref "U4") (pin "31") (pinfunction "PD6(T1)_31") (pintype "bidirectional"))
    )
    (net (code "22") (name "MISO") (class "Default")
      (node (ref "J4") (pin "1") (pinfunction "1_1") (pintype "passive"))
      (node (ref "U4") (pin "39") (pinfunction "PB3(MISO/PDO/PCINT3)_39") (pintype "bidirectional"))
    )
    (net (code "23") (name "MOSI") (class "Default")
      (node (ref "J4") (pin "4") (pinfunction "4_4") (pintype "passive"))
      (node (ref "U4") (pin "38") (pinfunction "PB2(MOSI/PDI/PCINT2)_38") (pintype "bidirectional"))
    )
    (net (code "24") (name "Net-(A1-SIGNAL)") (class "Default")
      (node (ref "A1") (pin "FEED") (pinfunction "SIGNAL_FEED") (pintype "bidirectional"))
      (node (ref "B2") (pin "1") (pinfunction "IN_1") (pintype "bidirectional"))
      (node (ref "C2") (pin "1") (pinfunction "1_1") (pintype "passive"))
    )
    (net (code "25") (name "Net-(B2-GND-Pad2)") (class "Default")
      (node (ref "B2") (pin "2") (pinfunction "GND_2") (pintype "bidirectional"))
      (node (ref "C3") (pin "2") (pinfunction "2_2") (pintype "passive"))
    )
    (net (code "26") (name "Net-(B2-OUT1)") (class "Default")
      (node (ref "B2") (pin "4") (pinfunction "OUT1_4") (pintype "bidirectional"))
      (node (ref "U4") (pin "8") (pinfunction "RFP_8") (pintype "bidirectional"))
    )
    (net (code "27") (name "Net-(B2-OUT2)") (class "Default")
      (node (ref "B2") (pin "3") (pinfunction "OUT2_3") (pintype "bidirectional"))
      (node (ref "U4") (pin "9") (pinfunction "RFN_9") (pintype "bidirectional"))
    )
    (net (code "28") (name "Net-(B11-P)") (class "Default")
      (node (ref "B11") (pin "2") (pinfunction "P_2") (pintype "bidirectional"))
      (node (ref "B3") (pin "1A") (pinfunction "P_1A") (pintype "bidirectional"))
      (node (ref "B3") (pin "1B") (pinfunction "P_1B") (pintype "bidirectional"))
      (node (ref "C6") (pin "1") (pinfunction "1_1") (pintype "passive"))
      (node (ref "D3") (pin "A") (pinfunction "A_A") (pintype "passive"))
      (node (ref "U2") (pin "3") (pinfunction "VBAT_3") (pintype "power_in"))
      (node (ref "V30") (pin "P1") (pinfunction "N_P1") (pintype "bidirectional"))
      (node (ref "V31") (pin "P1") (pinfunction "N_P1") (pintype "bidirectional"))
      (node (ref "V32") (pin "P1") (pinfunction "N_P1") (pintype "bidirectional"))
      (node (ref "V33") (pin "P1") (pinfunction "N_P1") (pintype "bidirectional"))
      (node (ref "V34") (pin "P1") (pinfunction "N_P1") (pintype "bidirectional"))
      (node (ref "V36") (pin "P1") (pinfunction "N_P1") (pintype "bidirectional"))
      (node (ref "V6") (pin "P1") (pinfunction "N_P1") (pintype "bidirectional"))
    )
    (net (code "29") (name "Net-(C11-Pad1)") (class "Default")
      (node (ref "C11") (pin "1") (pinfunction "1_1") (pintype "passive"))
      (node (ref "U4") (pin "21") (pinfunction "DVDD_21") (pintype "bidirectional"))
      (node (ref "U4") (pin "22") (pinfunction "DVDD_22") (pintype "bidirectional"))
    )
    (net (code "30") (name "Net-(D1-PadA1)") (class "Default")
      (node (ref "D1") (pin "A1") (pinfunction "A1_A1") (pintype "passive"))
      (node (ref "R3") (pin "1") (pinfunction "1_1") (pintype "passive"))
    )
    (net (code "31") (name "Net-(D1-PadC2)") (class "Default")
      (node (ref "D1") (pin "C2") (pinfunction "C2_C2") (pintype "passive"))
      (node (ref "R1") (pin "1") (pinfunction "1_1") (pintype "passive"))
    )
    (net (code "32") (name "Net-(D4-PadC1)") (class "Default")
      (node (ref "D4") (pin "C1") (pinfunction "C1_C1") (pintype "passive"))
      (node (ref "R15") (pin "2") (pinfunction "2_2") (pintype "passive"))
    )
    (net (code "33") (name "Net-(D4-PadC2)") (class "Default")
      (node (ref "D4") (pin "C2") (pinfunction "C2_C2") (pintype "passive"))
      (node (ref "R16") (pin "2") (pinfunction "2_2") (pintype "passive"))
    )
    (net (code "34") (name "Net-(D5-PadA1)") (class "Default")
      (node (ref "D5") (pin "A1") (pinfunction "A1_A1") (pintype "passive"))
      (node (ref "R14") (pin "1") (pinfunction "1_1") (pintype "passive"))
    )
    (net (code "35") (name "Net-(D5-PadA2)") (class "Default")
      (node (ref "D5") (pin "A2") (pinfunction "A2_A2") (pintype "passive"))
      (node (ref "R13") (pin "1") (pinfunction "1_1") (pintype "passive"))
    )
    (net (code "36") (name "Net-(D6-PadC1)") (class "Default")
      (node (ref "D6") (pin "C1") (pinfunction "C1_C1") (pintype "passive"))
      (node (ref "R18") (pin "2") (pinfunction "2_2") (pintype "passive"))
    )
    (net (code "37") (name "Net-(D6-PadC2)") (class "Default")
      (node (ref "D6") (pin "C2") (pinfunction "C2_C2") (pintype "passive"))
      (node (ref "R17") (pin "2") (pinfunction "2_2") (pintype "passive"))
    )
    (net (code "38") (name "Net-(S2-C)") (class "Default")
      (node (ref "S2") (pin "2") (pinfunction "C_2") (pintype "bidirectional"))
      (node (ref "U5") (pin "12") (pinfunction "2S_12") (pintype "bidirectional"))
      (node (ref "U5") (pin "4") (pinfunction "1S_4") (pintype "bidirectional"))
    )
    (net (code "39") (name "Net-(U2-PROG)") (class "Default")
      (node (ref "R7") (pin "1") (pinfunction "1_1") (pintype "passive"))
      (node (ref "U2") (pin "5") (pinfunction "PROG_5") (pintype "input"))
    )
    (net (code "40") (name "Net-(U2-STAT)") (class "Default")
      (node (ref "R1") (pin "2") (pinfunction "2_2") (pintype "passive"))
      (node (ref "R3") (pin "2") (pinfunction "2_2") (pintype "passive"))
      (node (ref "U2") (pin "1") (pinfunction "STAT_1") (pintype "output"))
    )
    (net (code "41") (name "Net-(U4-AVDD)") (class "Default")
      (node (ref "C13") (pin "1") (pinfunction "1_1") (pintype "passive"))
      (node (ref "U4") (pin "60") (pinfunction "AVDD_60") (pintype "bidirectional"))
    )
    (net (code "42") (name "Net-(U4-PG0(DIG3))") (class "Default")
      (node (ref "D6") (pin "A2") (pinfunction "A2_A2") (pintype "passive"))
      (node (ref "U4") (pin "14") (pinfunction "PG0(DIG3)_14") (pintype "bidirectional"))
    )
    (net (code "43") (name "Net-(U4-PG1(DIG1))") (class "Default")
      (node (ref "D6") (pin "A1") (pinfunction "A1_A1") (pintype "passive"))
      (node (ref "U4") (pin "15") (pinfunction "PG1(DIG1)_15") (pintype "bidirectional"))
    )
    (net (code "44") (name "Net-(U4-XTAL1)") (class "Default")
      (node (ref "C14") (pin "1") (pinfunction "1_1") (pintype "passive"))
      (node (ref "U4") (pin "57") (pinfunction "XTAL1_57") (pintype "bidirectional"))
      (node (ref "Y1") (pin "3") (pinfunction "2_3") (pintype "passive"))
    )
    (net (code "45") (name "Net-(U4-XTAL2)") (class "Default")
      (node (ref "C15") (pin "1") (pinfunction "1_1") (pintype "passive"))
      (node (ref "U4") (pin "56") (pinfunction "XTAL2_56") (pintype "bidirectional"))
      (node (ref "Y1") (pin "1") (pinfunction "1_1") (pintype "passive"))
    )
    (net (code "46") (name "PITCH") (class "Default")
      (node (ref "J3") (pin "V") (pinfunction "V_V") (pintype "bidirectional"))
      (node (ref "J8") (pin "V") (pinfunction "V_V") (pintype "bidirectional"))
      (node (ref "U4") (pin "2") (pinfunction "PF3(ADC3/DIG4)_2") (pintype "bidirectional"))
    )
    (net (code "47") (name "RESET") (class "Default")
      (node (ref "B1") (pin "1") (pinfunction "1_1") (pintype "passive"))
      (node (ref "B1") (pin "2") (pinfunction "1_2") (pintype "passive"))
      (node (ref "C1") (pin "1") (pinfunction "1_1") (pintype "passive"))
      (node (ref "J4") (pin "5") (pinfunction "5_5") (pintype "passive"))
      (node (ref "R2") (pin "1") (pinfunction "1_1") (pintype "passive"))
      (node (ref "U4") (pin "12") (pinfunction "RSTN_12") (pintype "bidirectional"))
    )
    (net (code "48") (name "RF") (class "Default")
      (node (ref "D4") (pin "A1") (pinfunction "A1_A1") (pintype "passive"))
      (node (ref "U4") (pin "16") (pinfunction "PG2(AMR)_16") (pintype "bidirectional"))
    )
    (net (code "49") (name "ROLL") (class "Default")
      (node (ref "J3") (pin "H") (pinfunction "H_H") (pintype "bidirectional"))
      (node (ref "J8") (pin "H") (pinfunction "H_H") (pintype "bidirectional"))
      (node (ref "U4") (pin "1") (pinfunction "PF2(ADC2/DIG2)_1") (pintype "bidirectional"))
    )
    (net (code "50") (name "RXI") (class "Default")
      (node (ref "U3") (pin "5") (pinfunction "RXD_5") (pintype "input"))
      (node (ref "U5") (pin "10") (pinfunction "3Z_10") (pintype "bidirectional"))
    )
    (net (code "51") (name "RXI-0") (class "Default")
      (node (ref "U4") (pin "47") (pinfunction "PE1(TXD0)_47") (pintype "bidirectional"))
      (node (ref "U5") (pin "11") (pinfunction "3Y0_11") (pintype "bidirectional"))
    )
    (net (code "52") (name "RXI-1") (class "Default")
      (node (ref "JP1") (pin "RXI") (pinfunction "2_RXI") (pintype "passive"))
      (node (ref "U5") (pin "9") (pinfunction "3Y1_9") (pintype "bidirectional"))
    )
    (net (code "53") (name "RXLED") (class "Default")
      (node (ref "D5") (pin "C2") (pinfunction "C2_C2") (pintype "passive"))
      (node (ref "U3") (pin "22") (pinfunction "RXLED_22") (pintype "input"))
    )
    (net (code "54") (name "SCK") (class "Default")
      (node (ref "J4") (pin "3") (pinfunction "3_3") (pintype "passive"))
      (node (ref "U4") (pin "37") (pinfunction "PB1(SCK/PCINT1)_37") (pintype "bidirectional"))
    )
    (net (code "55") (name "SHIELD") (class "Default")
      (node (ref "B12") (pin "P2") (pinfunction "P2_P2") (pintype "bidirectional"))
    )
    (net (code "56") (name "THROTTLE") (class "Default")
      (node (ref "J2") (pin "V") (pinfunction "V_V") (pintype "bidirectional"))
      (node (ref "J7") (pin "V") (pinfunction "V_V") (pintype "bidirectional"))
      (node (ref "U4") (pin "64") (pinfunction "PF1(ADC1)_64") (pintype "bidirectional"))
    )
    (net (code "57") (name "TXLED") (class "Default")
      (node (ref "D5") (pin "C1") (pinfunction "C1_C1") (pintype "passive"))
      (node (ref "U3") (pin "23") (pinfunction "TXLED_23") (pintype "input"))
    )
    (net (code "58") (name "TXO") (class "Default")
      (node (ref "U3") (pin "1") (pinfunction "TXD_1") (pintype "output"))
      (node (ref "U5") (pin "6") (pinfunction "2Z_6") (pintype "bidirectional"))
    )
    (net (code "59") (name "TXO-0") (class "Default")
      (node (ref "U4") (pin "46") (pinfunction "PE0(RXD0/PCINT8)_46") (pintype "bidirectional"))
      (node (ref "U5") (pin "7") (pinfunction "2Y0_7") (pintype "bidirectional"))
    )
    (net (code "60") (name "TXO-1") (class "Default")
      (node (ref "JP1") (pin "TXO") (pinfunction "3_TXO") (pintype "passive"))
      (node (ref "U5") (pin "5") (pinfunction "2Y1_5") (pintype "bidirectional"))
    )
    (net (code "61") (name "USB_D_N") (class "Default")
      (node (ref "J1") (pin "2") (pinfunction "2-D-_2") (pintype "bidirectional"))
      (node (ref "U3") (pin "16") (pinfunction "USBDM_16") (pintype "bidirectional"))
    )
    (net (code "62") (name "USB_D_P") (class "Default")
      (node (ref "J1") (pin "3") (pinfunction "3-D+_3") (pintype "bidirectional"))
      (node (ref "U3") (pin "15") (pinfunction "USBDP_15") (pintype "bidirectional"))
    )
    (net (code "63") (name "VBAT") (class "Default")
      (node (ref "D2") (pin "C") (pinfunction "C_C") (pintype "passive"))
      (node (ref "D3") (pin "C") (pinfunction "C_C") (pintype "passive"))
      (node (ref "P2") (pin "T") (pinfunction "T_T") (pintype "bidirectional"))
      (node (ref "S1") (pin "2") (pinfunction "C_2") (pintype "bidirectional"))
    )
    (net (code "64") (name "VBUS") (class "Default")
      (node (ref "C5") (pin "1") (pinfunction "1_1") (pintype "passive"))
      (node (ref "D1") (pin "A2") (pinfunction "A2_A2") (pintype "passive"))
      (node (ref "D2") (pin "A") (pinfunction "A_A") (pintype "passive"))
      (node (ref "J1") (pin "1") (pinfunction "1-VCC_1") (pintype "bidirectional"))
      (node (ref "P1") (pin "T") (pinfunction "T_T") (pintype "bidirectional"))
      (node (ref "U2") (pin "4") (pinfunction "VDD_4") (pintype "power_in"))
      (node (ref "V1") (pin "P1") (pinfunction "N_P1") (pintype "bidirectional"))
      (node (ref "V2") (pin "P1") (pinfunction "N_P1") (pintype "bidirectional"))
      (node (ref "V23") (pin "P1") (pinfunction "N_P1") (pintype "bidirectional"))
      (node (ref "V24") (pin "P1") (pinfunction "N_P1") (pintype "bidirectional"))
      (node (ref "V26") (pin "P1") (pinfunction "N_P1") (pintype "bidirectional"))
      (node (ref "V27") (pin "P1") (pinfunction "N_P1") (pintype "bidirectional"))
      (node (ref "V28") (pin "P1") (pinfunction "N_P1") (pintype "bidirectional"))
    )
    (net (code "65") (name "VREG_IN") (class "Default")
      (node (ref "C7") (pin "1") (pinfunction "1_1") (pintype "passive"))
      (node (ref "C8") (pin "1") (pinfunction "1_1") (pintype "passive"))
      (node (ref "L1") (pin "RAW") (pinfunction "VIN_RAW") (pintype "bidirectional"))
      (node (ref "S1") (pin "1") (pinfunction "ON_1") (pintype "bidirectional"))
      (node (ref "U3") (pin "20") (pinfunction "VCC_20") (pintype "power_in"))
    )
    (net (code "66") (name "YAW") (class "Default")
      (node (ref "J2") (pin "H") (pinfunction "H_H") (pintype "bidirectional"))
      (node (ref "J7") (pin "H") (pinfunction "H_H") (pintype "bidirectional"))
      (node (ref "U4") (pin "63") (pinfunction "PF0(ADC0)_63") (pintype "bidirectional"))
    )
    (net (code "67") (name "unconnected-(J1-4-ID-Pad4)") (class "Default")
      (node (ref "J1") (pin "4") (pinfunction "4-ID_4") (pintype "bidirectional"))
    )
    (net (code "68") (name "unconnected-(L1-PadSCK)") (class "Default")
      (node (ref "L1") (pin "SCK") (pinfunction "SCK_SCK") (pintype "bidirectional"))
    )
    (net (code "69") (name "unconnected-(L1-PadSDI)") (class "Default")
      (node (ref "L1") (pin "SDI") (pinfunction "SDI_SDI") (pintype "bidirectional"))
    )
    (net (code "70") (name "unconnected-(L1-PadSDO)") (class "Default")
      (node (ref "L1") (pin "SDO") (pinfunction "SDO_SDO") (pintype "bidirectional"))
    )
    (net (code "71") (name "unconnected-(L1-Pad{slash}CS)") (class "Default")
      (node (ref "L1") (pin "/CS") (pinfunction "/CS_/CS") (pintype "bidirectional"))
    )
    (net (code "72") (name "unconnected-(L1-SCL-PadCL)") (class "Default")
      (node (ref "L1") (pin "CL") (pinfunction "SCL_CL") (pintype "bidirectional"))
    )
    (net (code "73") (name "unconnected-(L1-SDA-PadDA)") (class "Default")
      (node (ref "L1") (pin "DA") (pinfunction "SDA_DA") (pintype "bidirectional"))
    )
    (net (code "74") (name "unconnected-(S1-OFF-Pad3)") (class "Default")
      (node (ref "S1") (pin "3") (pinfunction "OFF_3") (pintype "bidirectional"))
    )
    (net (code "75") (name "unconnected-(U3-DCD-Pad10)") (class "Default")
      (node (ref "U3") (pin "10") (pinfunction "DCD_10") (pintype "input"))
    )
    (net (code "76") (name "unconnected-(U3-DSR-Pad9)") (class "Default")
      (node (ref "U3") (pin "9") (pinfunction "DSR_9") (pintype "input"))
    )
    (net (code "77") (name "unconnected-(U3-OSCI-Pad27)") (class "Default")
      (node (ref "U3") (pin "27") (pinfunction "OSCI_27") (pintype "input"))
    )
    (net (code "78") (name "unconnected-(U3-OSCO-Pad28)") (class "Default")
      (node (ref "U3") (pin "28") (pinfunction "OSCO_28") (pintype "output"))
    )
    (net (code "79") (name "unconnected-(U3-PWREN-Pad14)") (class "Default")
      (node (ref "U3") (pin "14") (pinfunction "PWREN_14") (pintype "input"))
    )
    (net (code "80") (name "unconnected-(U3-RESET-Pad19)") (class "Default")
      (node (ref "U3") (pin "19") (pinfunction "RESET_19") (pintype "input"))
    )
    (net (code "81") (name "unconnected-(U3-RI-Pad6)") (class "Default")
      (node (ref "U3") (pin "6") (pinfunction "RI_6") (pintype "input"))
    )
    (net (code "82") (name "unconnected-(U3-RTS-Pad3)") (class "Default")
      (node (ref "U3") (pin "3") (pinfunction "RTS_3") (pintype "output"))
    )
    (net (code "83") (name "unconnected-(U3-SLEEP-Pad12)") (class "Default")
      (node (ref "U3") (pin "12") (pinfunction "SLEEP_12") (pintype "input"))
    )
    (net (code "84") (name "unconnected-(U3-TXDEN-Pad13)") (class "Default")
      (node (ref "U3") (pin "13") (pinfunction "TXDEN_13") (pintype "input"))
    )
    (net (code "85") (name "unconnected-(U4-AREF-Pad62)") (class "Default")
      (node (ref "U4") (pin "62") (pinfunction "AREF_62") (pintype "bidirectional"))
    )
    (net (code "86") (name "unconnected-(U4-PB0(SSN{slash}PCINT0)-Pad36)") (class "Default")
      (node (ref "U4") (pin "36") (pinfunction "PB0(SSN/PCINT0)_36") (pintype "bidirectional"))
    )
    (net (code "87") (name "unconnected-(U4-PB6(OC1B{slash}PCINT6)-Pad42)") (class "Default")
      (node (ref "U4") (pin "42") (pinfunction "PB6(OC1B/PCINT6)_42") (pintype "bidirectional"))
    )
    (net (code "88") (name "unconnected-(U4-PB7(OC0A{slash}OC1C{slash}PCINT7)-Pad43)") (class "Default")
      (node (ref "U4") (pin "43") (pinfunction "PB7(OC0A/OC1C/PCINT7)_43") (pintype "bidirectional"))
    )
    (net (code "89") (name "unconnected-(U4-PD4(ICP1)-Pad29)") (class "Default")
      (node (ref "U4") (pin "29") (pinfunction "PD4(ICP1)_29") (pintype "bidirectional"))
    )
    (net (code "90") (name "unconnected-(U4-PD5(XCK1)-Pad30)") (class "Default")
      (node (ref "U4") (pin "30") (pinfunction "PD5(XCK1)_30") (pintype "bidirectional"))
    )
    (net (code "91") (name "unconnected-(U4-PE2(XCK0{slash}AIN0)-Pad48)") (class "Default")
      (node (ref "U4") (pin "48") (pinfunction "PE2(XCK0/AIN0)_48") (pintype "bidirectional"))
    )
    (net (code "92") (name "unconnected-(U4-PE3(OC3A{slash}AIN1)-Pad49)") (class "Default")
      (node (ref "U4") (pin "49") (pinfunction "PE3(OC3A/AIN1)_49") (pintype "bidirectional"))
    )
    (net (code "93") (name "unconnected-(U4-PF4(ADC4{slash}TCK)-Pad3)") (class "Default")
      (node (ref "U4") (pin "3") (pinfunction "PF4(ADC4/TCK)_3") (pintype "bidirectional"))
    )
    (net (code "94") (name "unconnected-(U4-PF5(ADC5{slash}TMS)-Pad4)") (class "Default")
      (node (ref "U4") (pin "4") (pinfunction "PF5(ADC5/TMS)_4") (pintype "bidirectional"))
    )
    (net (code "95") (name "unconnected-(U4-PF6(ADC6{slash}TDO)-Pad5)") (class "Default")
      (node (ref "U4") (pin "5") (pinfunction "PF6(ADC6/TDO)_5") (pintype "bidirectional"))
    )
    (net (code "96") (name "unconnected-(U4-PF7(ADC7{slash}TDI)-Pad6)") (class "Default")
      (node (ref "U4") (pin "6") (pinfunction "PF7(ADC7/TDI)_6") (pintype "bidirectional"))
    )
    (net (code "97") (name "unconnected-(U4-PG3(TOSC2)-Pad17)") (class "Default")
      (node (ref "U4") (pin "17") (pinfunction "PG3(TOSC2)_17") (pintype "bidirectional"))
    )
    (net (code "98") (name "unconnected-(U4-PG4(TOSC1)-Pad18)") (class "Default")
      (node (ref "U4") (pin "18") (pinfunction "PG4(TOSC1)_18") (pintype "bidirectional"))
    )
    (net (code "99") (name "unconnected-(U4-PG5(OC0B)-Pad19)") (class "Default")
      (node (ref "U4") (pin "19") (pinfunction "PG5(OC0B)_19") (pintype "bidirectional"))
    )
    (net (code "100") (name "unconnected-(U4-RSTON-Pad13)") (class "Default")
      (node (ref "U4") (pin "13") (pinfunction "RSTON_13") (pintype "bidirectional"))
    )
  )
)
